# SCH_STEMI_XB3_0_LneFollower_2023-01-25.net
KiCad netlist of a schematic drawn in EasyEDA
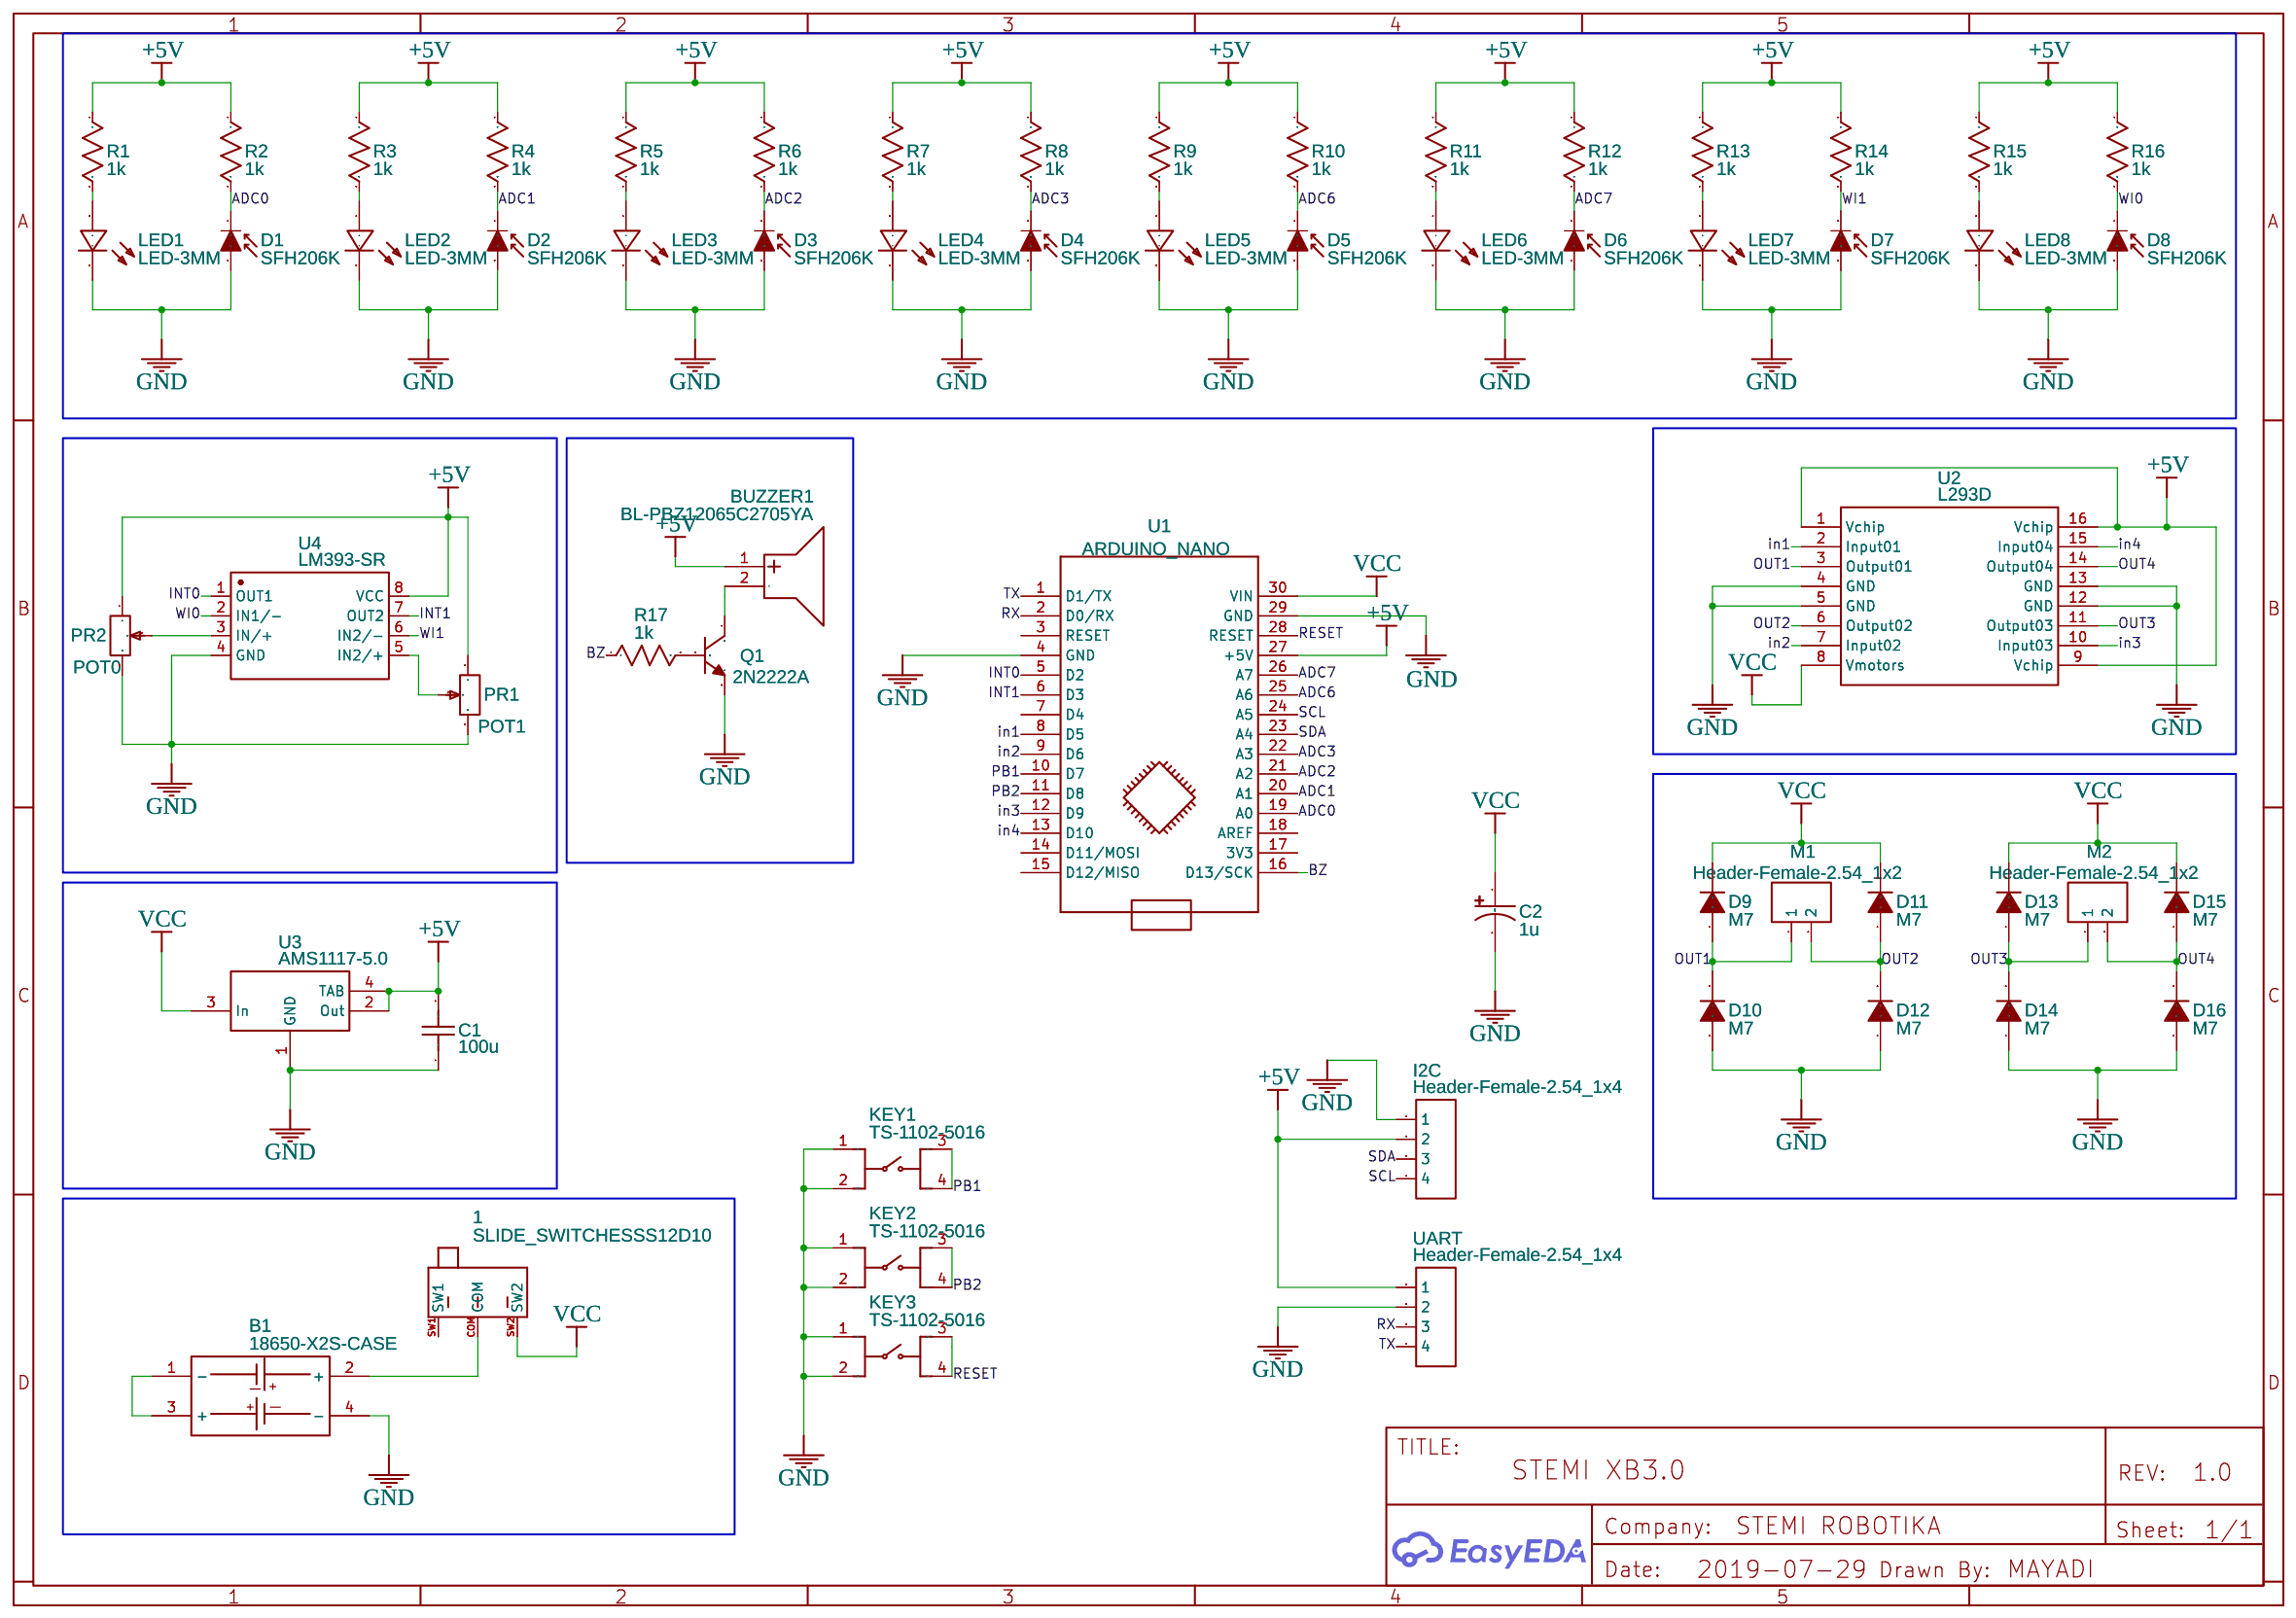
[diagram p0: schematic sheet]

(export (version "E")
  (design (tool "Eeschema 10.0.6"))
  (components
    (comp (ref "1")
      (value "SLIDE_SWITCHESSS12D10")
      (fields (field (name "BOM_Manufacturer Part") "?"))
      (libsource (lib "") (part "Unknown_235_650"))
    )
    (comp (ref "B1")
      (value "18650-X2S-CASE")
      (fields (field (name "BOM_Manufacturer Part") "18650-X2S"))
      (libsource (lib "") (part "Unknown_70_690"))
    )
    (comp (ref "BUZZER1")
      (value "BL-PBZ12065C2705YA")
      (fields (field (name "BOM_Supplier Part") "C249440"))
      (libsource (lib "") (part "Unknown_390_290"))
    )
    (comp (ref "C1")
      (value "100u")
      (fields (field (name "BOM_Manufacturer Part") "?"))
      (libsource (lib "") (part "Cap_1206_US"))
    )
    (comp (ref "C2")
      (value "1u")
      (fields (field (name "BOM_Manufacturer Part") "?"))
      (libsource (lib "") (part "Cap_Electrolytic(TH)_D6.3XF2.5_US"))
    )
    (comp (ref "D1")
      (value "SFH206K")
      (fields (field (name "BOM_Manufacturer Part") "?"))
      (libsource (lib "") (part "Unknown_110_110"))
    )
    (comp (ref "D2")
      (value "SFH206K")
      (fields (field (name "BOM_Manufacturer Part") "?"))
      (libsource (lib "") (part "Unknown_245_110"))
    )
    (comp (ref "D3")
      (value "SFH206K")
      (fields (field (name "BOM_Manufacturer Part") "?"))
      (libsource (lib "") (part "Unknown_380_110"))
    )
    (comp (ref "D4")
      (value "SFH206K")
      (fields (field (name "BOM_Manufacturer Part") "?"))
      (libsource (lib "") (part "Unknown_515_110"))
    )
    (comp (ref "D5")
      (value "SFH206K")
      (fields (field (name "BOM_Manufacturer Part") "?"))
      (libsource (lib "") (part "Unknown_650_110"))
    )
    (comp (ref "D6")
      (value "SFH206K")
      (fields (field (name "BOM_Manufacturer Part") "?"))
      (libsource (lib "") (part "Unknown_790_110"))
    )
    (comp (ref "D7")
      (value "SFH206K")
      (fields (field (name "BOM_Manufacturer Part") "?"))
      (libsource (lib "") (part "Unknown_925_110"))
    )
    (comp (ref "D8")
      (value "SFH206K")
      (fields (field (name "BOM_Manufacturer Part") "?"))
      (libsource (lib "") (part "Unknown_1065_110"))
    )
    (comp (ref "D9")
      (value "M7")
      (fields (field (name "BOM_Supplier Part") "undefined"))
      (libsource (lib "") (part "Unknown_860_450"))
    )
    (comp (ref "D10")
      (value "M7")
      (fields (field (name "BOM_Supplier Part") "undefined"))
      (libsource (lib "") (part "Unknown_860_505"))
    )
    (comp (ref "D11")
      (value "M7")
      (fields (field (name "BOM_Supplier Part") "undefined"))
      (libsource (lib "") (part "Unknown_945_450"))
    )
    (comp (ref "D12")
      (value "M7")
      (fields (field (name "BOM_Supplier Part") "undefined"))
      (libsource (lib "") (part "Unknown_945_505"))
    )
    (comp (ref "D13")
      (value "M7")
      (fields (field (name "BOM_Supplier Part") "undefined"))
      (libsource (lib "") (part "Unknown_1010_450"))
    )
    (comp (ref "D14")
      (value "M7")
      (fields (field (name "BOM_Supplier Part") "undefined"))
      (libsource (lib "") (part "Unknown_1010_505"))
    )
    (comp (ref "D15")
      (value "M7")
      (fields (field (name "BOM_Supplier Part") "undefined"))
      (libsource (lib "") (part "Unknown_1095_450"))
    )
    (comp (ref "D16")
      (value "M7")
      (fields (field (name "BOM_Supplier Part") "undefined"))
      (libsource (lib "") (part "Unknown_1095_505"))
    )
    (comp (ref "I2C")
      (value "Header-Female-2.54_1x4")
      (fields (field (name "BOM_Supplier Part") "C124413"))
      (libsource (lib "") (part "Unknown_715_575"))
    )
    (comp (ref "KEY1")
      (value "TS-1102-5016")
      (fields (field (name "BOM_Supplier Part") "C111609"))
      (libsource (lib "") (part "Unknown_445_580"))
    )
    (comp (ref "KEY2")
      (value "TS-1102-5016")
      (fields (field (name "BOM_Supplier Part") "C111609"))
      (libsource (lib "") (part "Unknown_445_630"))
    )
    (comp (ref "KEY3")
      (value "TS-1102-5016")
      (fields (field (name "BOM_Supplier Part") "C111609"))
      (libsource (lib "") (part "Unknown_445_675"))
    )
    (comp (ref "LED1")
      (value "LED-3MM")
      (fields
        (field (name "BOM_Manufacturer Part") "204-10SURD/S530-A3")
        (field (name "BOM_Supplier Part") "C99772")
      )
      (libsource (lib "") (part "Unknown_45_115"))
    )
    (comp (ref "LED2")
      (value "LED-3MM")
      (fields
        (field (name "BOM_Manufacturer Part") "204-10SURD/S530-A3")
        (field (name "BOM_Supplier Part") "C99772")
      )
      (libsource (lib "") (part "Unknown_180_115"))
    )
    (comp (ref "LED3")
      (value "LED-3MM")
      (fields
        (field (name "BOM_Manufacturer Part") "204-10SURD/S530-A3")
        (field (name "BOM_Supplier Part") "C99772")
      )
      (libsource (lib "") (part "Unknown_315_115"))
    )
    (comp (ref "LED4")
      (value "LED-3MM")
      (fields
        (field (name "BOM_Manufacturer Part") "204-10SURD/S530-A3")
        (field (name "BOM_Supplier Part") "C99772")
      )
      (libsource (lib "") (part "Unknown_450_115"))
    )
    (comp (ref "LED5")
      (value "LED-3MM")
      (fields
        (field (name "BOM_Manufacturer Part") "204-10SURD/S530-A3")
        (field (name "BOM_Supplier Part") "C99772")
      )
      (libsource (lib "") (part "Unknown_585_115"))
    )
    (comp (ref "LED6")
      (value "LED-3MM")
      (fields
        (field (name "BOM_Manufacturer Part") "204-10SURD/S530-A3")
        (field (name "BOM_Supplier Part") "C99772")
      )
      (libsource (lib "") (part "Unknown_725_115"))
    )
    (comp (ref "LED7")
      (value "LED-3MM")
      (fields
        (field (name "BOM_Manufacturer Part") "204-10SURD/S530-A3")
        (field (name "BOM_Supplier Part") "C99772")
      )
      (libsource (lib "") (part "Unknown_860_115"))
    )
    (comp (ref "LED8")
      (value "LED-3MM")
      (fields
        (field (name "BOM_Manufacturer Part") "204-10SURD/S530-A3")
        (field (name "BOM_Supplier Part") "C99772")
      )
      (libsource (lib "") (part "Unknown_1000_115"))
    )
    (comp (ref "M1")
      (value "Header-Female-2.54_1x2")
      (fields
        (field (name "BOM_Manufacturer Part") "2.54-1*2PFemale")
        (field (name "BOM_Supplier Part") "C49661")
      )
      (libsource (lib "") (part "Unknown_905_455"))
    )
    (comp (ref "M2")
      (value "Header-Female-2.54_1x2")
      (fields
        (field (name "BOM_Manufacturer Part") "2.54-1*2PFemale")
        (field (name "BOM_Supplier Part") "C49661")
      )
      (libsource (lib "") (part "Unknown_1055_455"))
    )
    (comp (ref "PR1")
      (value "POT1")
      (fields
        (field (name "BOM_Manufacturer Part") "Precision adjustable resistance 3296W-1-304(300K)")
        (field (name "BOM_Supplier Part") "C62174")
      )
      (libsource (lib "") (part "Unknown_225_345"))
    )
    (comp (ref "PR2")
      (value "POT0")
      (fields
        (field (name "BOM_Manufacturer Part") "Precision adjustable resistance 3296W-1-304(300K)")
        (field (name "BOM_Supplier Part") "C62174")
      )
      (libsource (lib "") (part "Unknown_60_315"))
    )
    (comp (ref "Q1")
      (value "2N2222A")
      (fields (field (name "BOM_Supplier Part") "C358533"))
      (libsource (lib "") (part "Unknown_350_325"))
    )
    (comp (ref "R1")
      (value "1k")
      (fields (field (name "BOM_Manufacturer Part") "?"))
      (libsource (lib "") (part "Res_AXIAL-0.4(1/4W)_US"))
    )
    (comp (ref "R2")
      (value "1k")
      (fields (field (name "BOM_Manufacturer Part") "?"))
      (libsource (lib "") (part "Res_AXIAL-0.4(1/4W)_US"))
    )
    (comp (ref "R3")
      (value "1k")
      (fields (field (name "BOM_Manufacturer Part") "?"))
      (libsource (lib "") (part "Res_AXIAL-0.4(1/4W)_US"))
    )
    (comp (ref "R4")
      (value "1k")
      (fields (field (name "BOM_Manufacturer Part") "?"))
      (libsource (lib "") (part "Res_AXIAL-0.4(1/4W)_US"))
    )
    (comp (ref "R5")
      (value "1k")
      (fields (field (name "BOM_Manufacturer Part") "?"))
      (libsource (lib "") (part "Res_AXIAL-0.4(1/4W)_US"))
    )
    (comp (ref "R6")
      (value "1k")
      (fields (field (name "BOM_Manufacturer Part") "?"))
      (libsource (lib "") (part "Res_AXIAL-0.4(1/4W)_US"))
    )
    (comp (ref "R7")
      (value "1k")
      (fields (field (name "BOM_Manufacturer Part") "?"))
      (libsource (lib "") (part "Res_AXIAL-0.4(1/4W)_US"))
    )
    (comp (ref "R8")
      (value "1k")
      (fields (field (name "BOM_Manufacturer Part") "?"))
      (libsource (lib "") (part "Res_AXIAL-0.4(1/4W)_US"))
    )
    (comp (ref "R9")
      (value "1k")
      (fields (field (name "BOM_Manufacturer Part") "?"))
      (libsource (lib "") (part "Res_AXIAL-0.4(1/4W)_US"))
    )
    (comp (ref "R10")
      (value "1k")
      (fields (field (name "BOM_Manufacturer Part") "?"))
      (libsource (lib "") (part "Res_AXIAL-0.4(1/4W)_US"))
    )
    (comp (ref "R11")
      (value "1k")
      (fields (field (name "BOM_Manufacturer Part") "?"))
      (libsource (lib "") (part "Res_AXIAL-0.4(1/4W)_US"))
    )
    (comp (ref "R12")
      (value "1k")
      (fields (field (name "BOM_Manufacturer Part") "?"))
      (libsource (lib "") (part "Res_AXIAL-0.4(1/4W)_US"))
    )
    (comp (ref "R13")
      (value "1k")
      (fields (field (name "BOM_Manufacturer Part") "?"))
      (libsource (lib "") (part "Res_AXIAL-0.4(1/4W)_US"))
    )
    (comp (ref "R14")
      (value "1k")
      (fields (field (name "BOM_Manufacturer Part") "?"))
      (libsource (lib "") (part "Res_AXIAL-0.4(1/4W)_US"))
    )
    (comp (ref "R15")
      (value "1k")
      (fields (field (name "BOM_Manufacturer Part") "?"))
      (libsource (lib "") (part "Res_AXIAL-0.4(1/4W)_US"))
    )
    (comp (ref "R16")
      (value "1k")
      (fields (field (name "BOM_Manufacturer Part") "?"))
      (libsource (lib "") (part "Res_AXIAL-0.4(1/4W)_US"))
    )
    (comp (ref "R17")
      (value "1k")
      (fields (field (name "BOM_Manufacturer Part") "?"))
      (libsource (lib "") (part "Res_AXIAL-0.4(1/4W)_US_1"))
    )
    (comp (ref "U1")
      (value "ARDUINO_NANO")
      (fields (field (name "BOM_Manufacturer Part") "?"))
      (libsource (lib "") (part "Unknown_580_370"))
    )
    (comp (ref "U2")
      (value "L293D")
      (fields (field (name "BOM_Supplier Part") "C12340"))
      (libsource (lib "") (part "Unknown_925_340"))
    )
    (comp (ref "U3")
      (value "AMS1117-5.0")
      (fields (field (name "BOM_Supplier Part") "C6187"))
      (libsource (lib "") (part "Unknown_140_510"))
    )
    (comp (ref "U4")
      (value "LM393-SR")
      (fields (field (name "BOM_Supplier Part") "C93150"))
      (libsource (lib "") (part "Unknown_150_310"))
    )
    (comp (ref "UART")
      (value "Header-Female-2.54_1x4")
      (fields (field (name "BOM_Supplier Part") "C124413"))
      (libsource (lib "") (part "Unknown_715_660"))
    )
  )
  (nets
    (net (code "1") (name "+5V") (class "Default")
      (node (ref "BUZZER1") (pin "1") (pinfunction "+_1") (pintype "unspecified"))
      (node (ref "C1") (pin "2") (pinfunction "2_2") (pintype "unspecified"))
      (node (ref "I2C") (pin "2") (pinfunction "2_2") (pintype "input"))
      (node (ref "PR1") (pin "1") (pinfunction "1_1") (pintype "input"))
      (node (ref "PR2") (pin "1") (pinfunction "1_1") (pintype "input"))
      (node (ref "R1") (pin "1") (pinfunction "1_1") (pintype "unspecified"))
      (node (ref "R10") (pin "1") (pinfunction "1_1") (pintype "unspecified"))
      (node (ref "R11") (pin "1") (pinfunction "1_1") (pintype "unspecified"))
      (node (ref "R12") (pin "1") (pinfunction "1_1") (pintype "unspecified"))
      (node (ref "R13") (pin "1") (pinfunction "1_1") (pintype "unspecified"))
      (node (ref "R14") (pin "1") (pinfunction "1_1") (pintype "unspecified"))
      (node (ref "R15") (pin "1") (pinfunction "1_1") (pintype "unspecified"))
      (node (ref "R16") (pin "1") (pinfunction "1_1") (pintype "unspecified"))
      (node (ref "R2") (pin "1") (pinfunction "1_1") (pintype "unspecified"))
      (node (ref "R3") (pin "1") (pinfunction "1_1") (pintype "unspecified"))
      (node (ref "R4") (pin "1") (pinfunction "1_1") (pintype "unspecified"))
      (node (ref "R5") (pin "1") (pinfunction "1_1") (pintype "unspecified"))
      (node (ref "R6") (pin "1") (pinfunction "1_1") (pintype "unspecified"))
      (node (ref "R7") (pin "1") (pinfunction "1_1") (pintype "unspecified"))
      (node (ref "R8") (pin "1") (pinfunction "1_1") (pintype "unspecified"))
      (node (ref "R9") (pin "1") (pinfunction "1_1") (pintype "unspecified"))
      (node (ref "U1") (pin "27") (pinfunction "+5V_27") (pintype "unspecified"))
      (node (ref "U2") (pin "1") (pinfunction "Vchip_1") (pintype "unspecified"))
      (node (ref "U2") (pin "16") (pinfunction "Vchip_16") (pintype "unspecified"))
      (node (ref "U2") (pin "9") (pinfunction "Vchip_9") (pintype "unspecified"))
      (node (ref "U3") (pin "2") (pinfunction "Out_2") (pintype "unspecified"))
      (node (ref "U3") (pin "4") (pinfunction "TAB_4") (pintype "unspecified"))
      (node (ref "U4") (pin "8") (pinfunction "VCC_8") (pintype "unspecified"))
      (node (ref "UART") (pin "1") (pinfunction "1_1") (pintype "input"))
    )
    (net (code "2") (name "/ADC0") (class "Default")
      (node (ref "D1") (pin "1") (pinfunction "K_1") (pintype "unspecified"))
      (node (ref "R2") (pin "2") (pinfunction "2_2") (pintype "unspecified"))
      (node (ref "U1") (pin "19") (pinfunction "A0_19") (pintype "unspecified"))
    )
    (net (code "3") (name "/ADC1") (class "Default")
      (node (ref "D2") (pin "1") (pinfunction "K_1") (pintype "unspecified"))
      (node (ref "R4") (pin "2") (pinfunction "2_2") (pintype "unspecified"))
      (node (ref "U1") (pin "20") (pinfunction "A1_20") (pintype "unspecified"))
    )
    (net (code "4") (name "/ADC2") (class "Default")
      (node (ref "D3") (pin "1") (pinfunction "K_1") (pintype "unspecified"))
      (node (ref "R6") (pin "2") (pinfunction "2_2") (pintype "unspecified"))
      (node (ref "U1") (pin "21") (pinfunction "A2_21") (pintype "unspecified"))
    )
    (net (code "5") (name "/ADC3") (class "Default")
      (node (ref "D4") (pin "1") (pinfunction "K_1") (pintype "unspecified"))
      (node (ref "R8") (pin "2") (pinfunction "2_2") (pintype "unspecified"))
      (node (ref "U1") (pin "22") (pinfunction "A3_22") (pintype "unspecified"))
    )
    (net (code "6") (name "/ADC6") (class "Default")
      (node (ref "D5") (pin "1") (pinfunction "K_1") (pintype "unspecified"))
      (node (ref "R10") (pin "2") (pinfunction "2_2") (pintype "unspecified"))
      (node (ref "U1") (pin "25") (pinfunction "A6_25") (pintype "unspecified"))
    )
    (net (code "7") (name "/ADC7") (class "Default")
      (node (ref "D6") (pin "1") (pinfunction "K_1") (pintype "unspecified"))
      (node (ref "R12") (pin "2") (pinfunction "2_2") (pintype "unspecified"))
      (node (ref "U1") (pin "26") (pinfunction "A7_26") (pintype "unspecified"))
    )
    (net (code "8") (name "/BZ") (class "Default")
      (node (ref "R17") (pin "1") (pinfunction "1_1") (pintype "unspecified"))
      (node (ref "U1") (pin "16") (pinfunction "D13/SCK_16") (pintype "unspecified"))
    )
    (net (code "9") (name "/INT0") (class "Default")
      (node (ref "U1") (pin "5") (pinfunction "D2_5") (pintype "unspecified"))
      (node (ref "U4") (pin "1") (pinfunction "OUT1_1") (pintype "unspecified"))
    )
    (net (code "10") (name "/INT1") (class "Default")
      (node (ref "U1") (pin "6") (pinfunction "D3_6") (pintype "unspecified"))
      (node (ref "U4") (pin "7") (pinfunction "OUT2_7") (pintype "unspecified"))
    )
    (net (code "11") (name "/OUT1") (class "Default")
      (node (ref "D10") (pin "2") (pinfunction "K_2") (pintype "unspecified"))
      (node (ref "D9") (pin "1") (pinfunction "A_1") (pintype "unspecified"))
      (node (ref "M1") (pin "1") (pinfunction "1_1") (pintype "input"))
      (node (ref "U2") (pin "3") (pinfunction "Output01_3") (pintype "unspecified"))
    )
    (net (code "12") (name "/OUT2") (class "Default")
      (node (ref "D11") (pin "1") (pinfunction "A_1") (pintype "unspecified"))
      (node (ref "D12") (pin "2") (pinfunction "K_2") (pintype "unspecified"))
      (node (ref "M1") (pin "2") (pinfunction "2_2") (pintype "input"))
      (node (ref "U2") (pin "6") (pinfunction "Output02_6") (pintype "unspecified"))
    )
    (net (code "13") (name "/OUT3") (class "Default")
      (node (ref "D13") (pin "1") (pinfunction "A_1") (pintype "unspecified"))
      (node (ref "D14") (pin "2") (pinfunction "K_2") (pintype "unspecified"))
      (node (ref "M2") (pin "1") (pinfunction "1_1") (pintype "input"))
      (node (ref "U2") (pin "11") (pinfunction "Output03_11") (pintype "unspecified"))
    )
    (net (code "14") (name "/OUT4") (class "Default")
      (node (ref "D15") (pin "1") (pinfunction "A_1") (pintype "unspecified"))
      (node (ref "D16") (pin "2") (pinfunction "K_2") (pintype "unspecified"))
      (node (ref "M2") (pin "2") (pinfunction "2_2") (pintype "input"))
      (node (ref "U2") (pin "14") (pinfunction "Output04_14") (pintype "unspecified"))
    )
    (net (code "15") (name "/PB1") (class "Default")
      (node (ref "KEY1") (pin "3") (pinfunction "3_3") (pintype "unspecified"))
      (node (ref "KEY1") (pin "4") (pinfunction "4_4") (pintype "unspecified"))
      (node (ref "U1") (pin "10") (pinfunction "D7_10") (pintype "unspecified"))
    )
    (net (code "16") (name "/PB2") (class "Default")
      (node (ref "KEY2") (pin "3") (pinfunction "3_3") (pintype "unspecified"))
      (node (ref "KEY2") (pin "4") (pinfunction "4_4") (pintype "unspecified"))
      (node (ref "U1") (pin "11") (pinfunction "D8_11") (pintype "unspecified"))
    )
    (net (code "17") (name "/RESET") (class "Default")
      (node (ref "KEY3") (pin "3") (pinfunction "3_3") (pintype "unspecified"))
      (node (ref "KEY3") (pin "4") (pinfunction "4_4") (pintype "unspecified"))
      (node (ref "U1") (pin "28") (pinfunction "RESET_28") (pintype "unspecified"))
    )
    (net (code "18") (name "/RX") (class "Default")
      (node (ref "U1") (pin "2") (pinfunction "D0/RX_2") (pintype "unspecified"))
      (node (ref "UART") (pin "3") (pinfunction "3_3") (pintype "input"))
    )
    (net (code "19") (name "/SCL") (class "Default")
      (node (ref "I2C") (pin "4") (pinfunction "4_4") (pintype "input"))
      (node (ref "U1") (pin "24") (pinfunction "A5_24") (pintype "unspecified"))
    )
    (net (code "20") (name "/SDA") (class "Default")
      (node (ref "I2C") (pin "3") (pinfunction "3_3") (pintype "input"))
      (node (ref "U1") (pin "23") (pinfunction "A4_23") (pintype "unspecified"))
    )
    (net (code "21") (name "/TX") (class "Default")
      (node (ref "U1") (pin "1") (pinfunction "D1/TX_1") (pintype "unspecified"))
      (node (ref "UART") (pin "4") (pinfunction "4_4") (pintype "input"))
    )
    (net (code "22") (name "/WI0") (class "Default")
      (node (ref "D8") (pin "1") (pinfunction "K_1") (pintype "unspecified"))
      (node (ref "R16") (pin "2") (pinfunction "2_2") (pintype "unspecified"))
      (node (ref "U4") (pin "2") (pinfunction "IN1/-_2") (pintype "unspecified"))
    )
    (net (code "23") (name "/WI1") (class "Default")
      (node (ref "D7") (pin "1") (pinfunction "K_1") (pintype "unspecified"))
      (node (ref "R14") (pin "2") (pinfunction "2_2") (pintype "unspecified"))
      (node (ref "U4") (pin "6") (pinfunction "IN2/-_6") (pintype "unspecified"))
    )
    (net (code "24") (name "/in1") (class "Default")
      (node (ref "U1") (pin "8") (pinfunction "D5_8") (pintype "unspecified"))
      (node (ref "U2") (pin "2") (pinfunction "Input01_2") (pintype "unspecified"))
    )
    (net (code "25") (name "/in2") (class "Default")
      (node (ref "U1") (pin "9") (pinfunction "D6_9") (pintype "unspecified"))
      (node (ref "U2") (pin "7") (pinfunction "Input02_7") (pintype "unspecified"))
    )
    (net (code "26") (name "/in3") (class "Default")
      (node (ref "U1") (pin "12") (pinfunction "D9_12") (pintype "unspecified"))
      (node (ref "U2") (pin "10") (pinfunction "Input03_10") (pintype "unspecified"))
    )
    (net (code "27") (name "/in4") (class "Default")
      (node (ref "U1") (pin "13") (pinfunction "D10_13") (pintype "unspecified"))
      (node (ref "U2") (pin "15") (pinfunction "Input04_15") (pintype "unspecified"))
    )
    (net (code "28") (name "GND") (class "Default")
      (node (ref "B1") (pin "4") (pinfunction "-_4") (pintype "unspecified"))
      (node (ref "C1") (pin "1") (pinfunction "1_1") (pintype "unspecified"))
      (node (ref "C2") (pin "2") (pinfunction "2_2") (pintype "unspecified"))
      (node (ref "D1") (pin "2") (pinfunction "A_2") (pintype "unspecified"))
      (node (ref "D10") (pin "1") (pinfunction "A_1") (pintype "unspecified"))
      (node (ref "D12") (pin "1") (pinfunction "A_1") (pintype "unspecified"))
      (node (ref "D14") (pin "1") (pinfunction "A_1") (pintype "unspecified"))
      (node (ref "D16") (pin "1") (pinfunction "A_1") (pintype "unspecified"))
      (node (ref "D2") (pin "2") (pinfunction "A_2") (pintype "unspecified"))
      (node (ref "D3") (pin "2") (pinfunction "A_2") (pintype "unspecified"))
      (node (ref "D4") (pin "2") (pinfunction "A_2") (pintype "unspecified"))
      (node (ref "D5") (pin "2") (pinfunction "A_2") (pintype "unspecified"))
      (node (ref "D6") (pin "2") (pinfunction "A_2") (pintype "unspecified"))
      (node (ref "D7") (pin "2") (pinfunction "A_2") (pintype "unspecified"))
      (node (ref "D8") (pin "2") (pinfunction "A_2") (pintype "unspecified"))
      (node (ref "I2C") (pin "1") (pinfunction "1_1") (pintype "input"))
      (node (ref "KEY1") (pin "1") (pinfunction "1_1") (pintype "unspecified"))
      (node (ref "KEY1") (pin "2") (pinfunction "2_2") (pintype "unspecified"))
      (node (ref "KEY2") (pin "1") (pinfunction "1_1") (pintype "unspecified"))
      (node (ref "KEY2") (pin "2") (pinfunction "2_2") (pintype "unspecified"))
      (node (ref "KEY3") (pin "1") (pinfunction "1_1") (pintype "unspecified"))
      (node (ref "KEY3") (pin "2") (pinfunction "2_2") (pintype "unspecified"))
      (node (ref "LED1") (pin "2") (pinfunction "-_2") (pintype "unspecified"))
      (node (ref "LED2") (pin "2") (pinfunction "-_2") (pintype "unspecified"))
      (node (ref "LED3") (pin "2") (pinfunction "-_2") (pintype "unspecified"))
      (node (ref "LED4") (pin "2") (pinfunction "-_2") (pintype "unspecified"))
      (node (ref "LED5") (pin "2") (pinfunction "-_2") (pintype "unspecified"))
      (node (ref "LED6") (pin "2") (pinfunction "-_2") (pintype "unspecified"))
      (node (ref "LED7") (pin "2") (pinfunction "-_2") (pintype "unspecified"))
      (node (ref "LED8") (pin "2") (pinfunction "-_2") (pintype "unspecified"))
      (node (ref "PR1") (pin "3") (pinfunction "3_3") (pintype "input"))
      (node (ref "PR2") (pin "3") (pinfunction "3_3") (pintype "input"))
      (node (ref "Q1") (pin "3") (pinfunction "E_3") (pintype "unspecified"))
      (node (ref "U1") (pin "29") (pinfunction "GND_29") (pintype "unspecified"))
      (node (ref "U1") (pin "4") (pinfunction "GND_4") (pintype "unspecified"))
      (node (ref "U2") (pin "12") (pinfunction "GND_12") (pintype "unspecified"))
      (node (ref "U2") (pin "13") (pinfunction "GND_13") (pintype "unspecified"))
      (node (ref "U2") (pin "4") (pinfunction "GND_4") (pintype "unspecified"))
      (node (ref "U2") (pin "5") (pinfunction "GND_5") (pintype "unspecified"))
      (node (ref "U3") (pin "1") (pinfunction "GND_1") (pintype "unspecified"))
      (node (ref "U4") (pin "4") (pinfunction "GND_4") (pintype "unspecified"))
      (node (ref "UART") (pin "2") (pinfunction "2_2") (pintype "input"))
    )
    (net (code "29") (name "Net-(1-PadCOM)") (class "Default")
      (node (ref "1") (pin "COM") (pinfunction "COM_COM") (pintype "bidirectional"))
      (node (ref "B1") (pin "2") (pinfunction "+_2") (pintype "unspecified"))
    )
    (net (code "30") (name "Net-(B1-+-Pad3)") (class "Default")
      (node (ref "B1") (pin "1") (pinfunction "-_1") (pintype "unspecified"))
      (node (ref "B1") (pin "3") (pinfunction "+_3") (pintype "unspecified"))
    )
    (net (code "31") (name "Net-(BUZZER1--)") (class "Default")
      (node (ref "BUZZER1") (pin "2") (pinfunction "-_2") (pintype "unspecified"))
      (node (ref "Q1") (pin "1") (pinfunction "C_1") (pintype "unspecified"))
    )
    (net (code "32") (name "Net-(LED1-+)") (class "Default")
      (node (ref "LED1") (pin "1") (pinfunction "+_1") (pintype "unspecified"))
      (node (ref "R1") (pin "2") (pinfunction "2_2") (pintype "unspecified"))
    )
    (net (code "33") (name "Net-(LED2-+)") (class "Default")
      (node (ref "LED2") (pin "1") (pinfunction "+_1") (pintype "unspecified"))
      (node (ref "R3") (pin "2") (pinfunction "2_2") (pintype "unspecified"))
    )
    (net (code "34") (name "Net-(LED3-+)") (class "Default")
      (node (ref "LED3") (pin "1") (pinfunction "+_1") (pintype "unspecified"))
      (node (ref "R5") (pin "2") (pinfunction "2_2") (pintype "unspecified"))
    )
    (net (code "35") (name "Net-(LED4-+)") (class "Default")
      (node (ref "LED4") (pin "1") (pinfunction "+_1") (pintype "unspecified"))
      (node (ref "R7") (pin "2") (pinfunction "2_2") (pintype "unspecified"))
    )
    (net (code "36") (name "Net-(LED5-+)") (class "Default")
      (node (ref "LED5") (pin "1") (pinfunction "+_1") (pintype "unspecified"))
      (node (ref "R9") (pin "2") (pinfunction "2_2") (pintype "unspecified"))
    )
    (net (code "37") (name "Net-(LED6-+)") (class "Default")
      (node (ref "LED6") (pin "1") (pinfunction "+_1") (pintype "unspecified"))
      (node (ref "R11") (pin "2") (pinfunction "2_2") (pintype "unspecified"))
    )
    (net (code "38") (name "Net-(LED7-+)") (class "Default")
      (node (ref "LED7") (pin "1") (pinfunction "+_1") (pintype "unspecified"))
      (node (ref "R13") (pin "2") (pinfunction "2_2") (pintype "unspecified"))
    )
    (net (code "39") (name "Net-(LED8-+)") (class "Default")
      (node (ref "LED8") (pin "1") (pinfunction "+_1") (pintype "unspecified"))
      (node (ref "R15") (pin "2") (pinfunction "2_2") (pintype "unspecified"))
    )
    (net (code "40") (name "Net-(Q1-B)") (class "Default")
      (node (ref "Q1") (pin "2") (pinfunction "B_2") (pintype "unspecified"))
      (node (ref "R17") (pin "2") (pinfunction "2_2") (pintype "unspecified"))
    )
    (net (code "41") (name "Net-(U4-IN2{slash}+)") (class "Default")
      (node (ref "PR1") (pin "2") (pinfunction "2_2") (pintype "input"))
      (node (ref "U4") (pin "5") (pinfunction "IN2/+_5") (pintype "unspecified"))
    )
    (net (code "42") (name "Net-(U4-IN{slash}+)") (class "Default")
      (node (ref "PR2") (pin "2") (pinfunction "2_2") (pintype "input"))
      (node (ref "U4") (pin "3") (pinfunction "IN/+_3") (pintype "unspecified"))
    )
    (net (code "43") (name "VCC") (class "Default")
      (node (ref "1") (pin "SW2") (pinfunction "SW2_SW2") (pintype "bidirectional"))
      (node (ref "C2") (pin "1") (pinfunction "1_1") (pintype "unspecified"))
      (node (ref "D11") (pin "2") (pinfunction "K_2") (pintype "unspecified"))
      (node (ref "D13") (pin "2") (pinfunction "K_2") (pintype "unspecified"))
      (node (ref "D15") (pin "2") (pinfunction "K_2") (pintype "unspecified"))
      (node (ref "D9") (pin "2") (pinfunction "K_2") (pintype "unspecified"))
      (node (ref "U1") (pin "30") (pinfunction "VIN_30") (pintype "unspecified"))
      (node (ref "U2") (pin "8") (pinfunction "Vmotors_8") (pintype "unspecified"))
      (node (ref "U3") (pin "3") (pinfunction "In_3") (pintype "unspecified"))
    )
    (net (code "44") (name "unconnected-(1-PadSW1)") (class "Default")
      (node (ref "1") (pin "SW1") (pinfunction "SW1_SW1") (pintype "bidirectional"))
    )
    (net (code "45") (name "unconnected-(U1-3V3-Pad17)") (class "Default")
      (node (ref "U1") (pin "17") (pinfunction "3V3_17") (pintype "unspecified"))
    )
    (net (code "46") (name "unconnected-(U1-AREF-Pad18)") (class "Default")
      (node (ref "U1") (pin "18") (pinfunction "AREF_18") (pintype "unspecified"))
    )
    (net (code "47") (name "unconnected-(U1-D4-Pad7)") (class "Default")
      (node (ref "U1") (pin "7") (pinfunction "D4_7") (pintype "unspecified"))
    )
    (net (code "48") (name "unconnected-(U1-D11{slash}MOSI-Pad14)") (class "Default")
      (node (ref "U1") (pin "14") (pinfunction "D11/MOSI_14") (pintype "unspecified"))
    )
    (net (code "49") (name "unconnected-(U1-D12{slash}MISO-Pad15)") (class "Default")
      (node (ref "U1") (pin "15") (pinfunction "D12/MISO_15") (pintype "unspecified"))
    )
    (net (code "50") (name "unconnected-(U1-RESET-Pad3)") (class "Default")
      (node (ref "U1") (pin "3") (pinfunction "RESET_3") (pintype "unspecified"))
    )
  )
)
